# Sheet2.net
KiCad netlist of a schematic drawn in Altium Designer
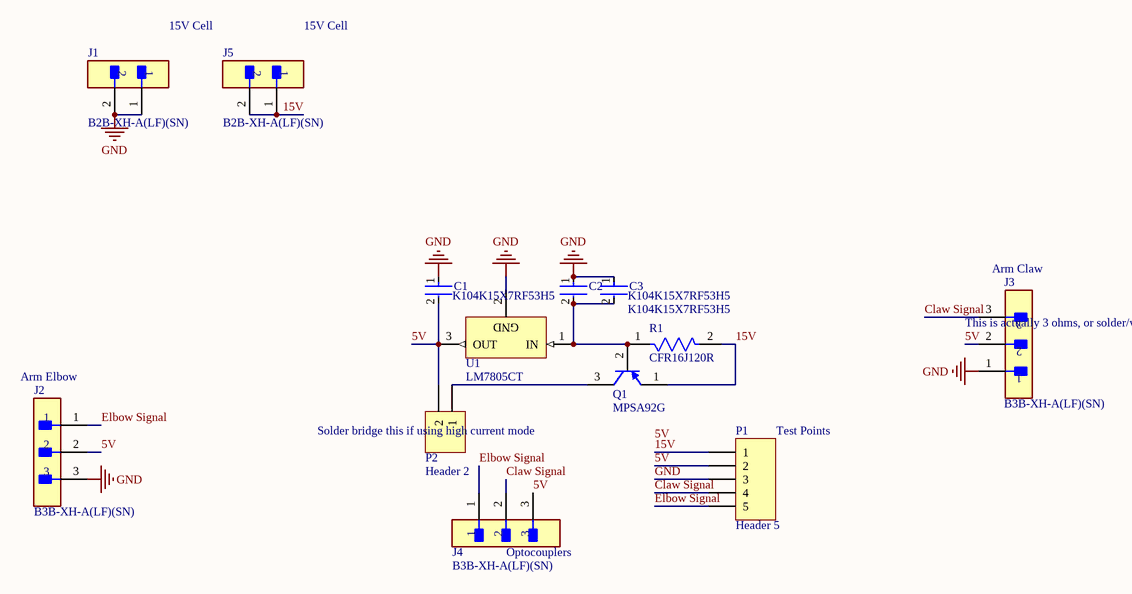
[diagram p0: Sheet2.SchDoc]

(export (version "E")
  (design (tool "Eeschema 10.0.6"))
  (components
    (comp (ref "C1")
      (value "K104K15X7RF53H5")
      (footprint "FP-K15H5-MFG")
      (description "CAP CER 0.1UF 50V X7R RADIAL")
      (fields (field (name "VOLTAGE") "50V") (field (name "TOLERANCE") "10%"))
      (libsource (lib "Altium Content Vault") (part "11868f565c42a9108669ba33697ecf6"))
    )
    (comp (ref "C2")
      (value "K104K15X7RF53H5")
      (footprint "FP-K15H5-MFG")
      (description "CAP CER 0.1UF 50V X7R RADIAL")
      (fields (field (name "VOLTAGE") "50V") (field (name "TOLERANCE") "10%"))
      (libsource (lib "Altium Content Vault") (part "11868f565c42a9108669ba33697ecf6"))
    )
    (comp (ref "C3")
      (value "K104K15X7RF53H5")
      (footprint "FP-K15H5-MFG")
      (description "CAP CER 0.1UF 50V X7R RADIAL")
      (fields (field (name "VOLTAGE") "50V") (field (name "TOLERANCE") "10%"))
      (libsource (lib "Altium Content Vault") (part "11868f565c42a9108669ba33697ecf6"))
    )
    (comp (ref "J1")
      (value "B2B-XH-A(LF)(SN)")
      (footprint "FP-B2B-XH-A_LF_SN-MFG")
      (description "CONN HEADER VERT 2POS 2.5MM")
      (libsource (lib "Altium Content Vault") (part "3bc925449376181038e59eaffc5286c"))
    )
    (comp (ref "J2")
      (value "B3B-XH-A(LF)(SN)")
      (footprint "FP-B3B-XH-A_LF_SN-MFG")
      (description "CONN HEADER VERT 3POS 2.5MM")
      (libsource (lib "") (part "0d3f023dd272f625e17a2be33dea85f_1"))
    )
    (comp (ref "J3")
      (value "B3B-XH-A(LF)(SN)")
      (footprint "FP-B3B-XH-A_LF_SN-MFG")
      (description "CONN HEADER VERT 3POS 2.5MM")
      (libsource (lib "") (part "0d3f023dd272f625e17a2be33dea85f_2"))
    )
    (comp (ref "J4")
      (value "B3B-XH-A(LF)(SN)")
      (footprint "FP-B3B-XH-A_LF_SN-MFG")
      (description "CONN HEADER VERT 3POS 2.5MM")
      (libsource (lib "Altium Content Vault") (part "0d3f023dd272f625e17a2be33dea85f"))
    )
    (comp (ref "J5")
      (value "B2B-XH-A(LF)(SN)")
      (footprint "FP-B2B-XH-A_LF_SN-MFG")
      (description "CONN HEADER VERT 2POS 2.5MM")
      (libsource (lib "Altium Content Vault") (part "3bc925449376181038e59eaffc5286c"))
    )
    (comp (ref "P1")
      (value "Header 5")
      (footprint "HDR1X5")
      (description "Header, 5-Pin")
      (fields (field (name "PUBLISHER") "Altium Limited"))
      (libsource (lib "Miscellaneous Connectors") (part "Header 5"))
    )
    (comp (ref "P2")
      (value "Header 2")
      (footprint "HDR1X2")
      (description "Header, 2-Pin")
      (fields (field (name "PUBLISHER") "Altium Limited"))
      (libsource (lib "Miscellaneous Connectors") (part "Header 2"))
    )
    (comp (ref "Q1")
      (value "MPSA92G")
      (footprint "ONSC-TO-92-3-29-11")
      (description "High Voltage Transistor, PNP Silicon, 3-Pin TO-92, Pb-Free, Bulk Box")
      (fields (field (name "MANUFACTURER") "On Semiconductor"))
      (libsource (lib "Altium Content Vault") (part "ONSC-PNP-E1B2C3-3"))
    )
    (comp (ref "R1")
      (value "CFR16J120R")
      (footprint "FP-CFR16-MFG")
      (description "RES 120 OHM 1/4W 5% AXIAL")
      (fields (field (name "TOLERANCE") "5%"))
      (libsource (lib "Altium Content Vault") (part "1029c3af85768c4190bb7ad29bc67b5"))
    )
    (comp (ref "U1")
      (value "LM7805CT")
      (footprint "FAIR-TO-220-3")
      (description "Positive Voltage Regulator, 5 V, 1 A, -40 to 125 degC, 3-Pin TO-220, RoHS, Tube")
      (fields (field (name "MANUFACTURER") "FairchildSemiconductor"))
      (libsource (lib "Altium Content Vault") (part "FAIR-LM7805CT-TO220-3"))
    )
  )
  (nets
    (net (code "1") (name "/5V") (class "Default")
      (node (ref "C1") (pin "2") (pinfunction "2_2") (pintype "passive"))
      (node (ref "J2") (pin "2") (pinfunction "2_2") (pintype "passive"))
      (node (ref "J3") (pin "2") (pinfunction "2_2") (pintype "passive"))
      (node (ref "J4") (pin "3") (pinfunction "3_3") (pintype "passive"))
      (node (ref "P1") (pin "2") (pinfunction "2_2") (pintype "passive"))
      (node (ref "P2") (pin "2") (pinfunction "2_2") (pintype "passive"))
      (node (ref "U1") (pin "3") (pinfunction "OUT_3") (pintype "output"))
    )
    (net (code "2") (name "/15V") (class "Default")
      (node (ref "J5") (pin "1") (pinfunction "1_1") (pintype "passive"))
      (node (ref "J5") (pin "2") (pinfunction "2_2") (pintype "passive"))
      (node (ref "P1") (pin "1") (pinfunction "1_1") (pintype "passive"))
      (node (ref "Q1") (pin "1") (pinfunction "E_1") (pintype "passive"))
      (node (ref "R1") (pin "2") (pinfunction "2_2") (pintype "passive"))
    )
    (net (code "3") (name "/Claw Signal") (class "Default")
      (node (ref "J3") (pin "3") (pinfunction "3_3") (pintype "passive"))
      (node (ref "J4") (pin "2") (pinfunction "2_2") (pintype "passive"))
      (node (ref "P1") (pin "4") (pinfunction "4_4") (pintype "passive"))
    )
    (net (code "4") (name "/Elbow Signal") (class "Default")
      (node (ref "J2") (pin "1") (pinfunction "1_1") (pintype "passive"))
      (node (ref "J4") (pin "1") (pinfunction "1_1") (pintype "passive"))
      (node (ref "P1") (pin "5") (pinfunction "5_5") (pintype "passive"))
    )
    (net (code "5") (name "GND") (class "Default")
      (node (ref "C1") (pin "1") (pinfunction "1_1") (pintype "passive"))
      (node (ref "C2") (pin "1") (pinfunction "1_1") (pintype "passive"))
      (node (ref "C3") (pin "1") (pinfunction "1_1") (pintype "passive"))
      (node (ref "J1") (pin "1") (pinfunction "1_1") (pintype "passive"))
      (node (ref "J1") (pin "2") (pinfunction "2_2") (pintype "passive"))
      (node (ref "J2") (pin "3") (pinfunction "3_3") (pintype "passive"))
      (node (ref "J3") (pin "1") (pinfunction "1_1") (pintype "passive"))
      (node (ref "P1") (pin "3") (pinfunction "3_3") (pintype "passive"))
      (node (ref "U1") (pin "2") (pinfunction "GND_2") (pintype "power_in"))
    )
    (net (code "6") (name "Net-(Q1-B)") (class "Default")
      (node (ref "C2") (pin "2") (pinfunction "2_2") (pintype "passive"))
      (node (ref "C3") (pin "2") (pinfunction "2_2") (pintype "passive"))
      (node (ref "Q1") (pin "2") (pinfunction "B_2") (pintype "passive"))
      (node (ref "R1") (pin "1") (pinfunction "1_1") (pintype "passive"))
      (node (ref "U1") (pin "1") (pinfunction "IN_1") (pintype "input"))
    )
    (net (code "7") (name "Net-(Q1-C)") (class "Default")
      (node (ref "P2") (pin "1") (pinfunction "1_1") (pintype "passive"))
      (node (ref "Q1") (pin "3") (pinfunction "C_3") (pintype "passive"))
    )
  )
)
